# sensor.net
KiCad netlist of a schematic drawn in Altium Designer
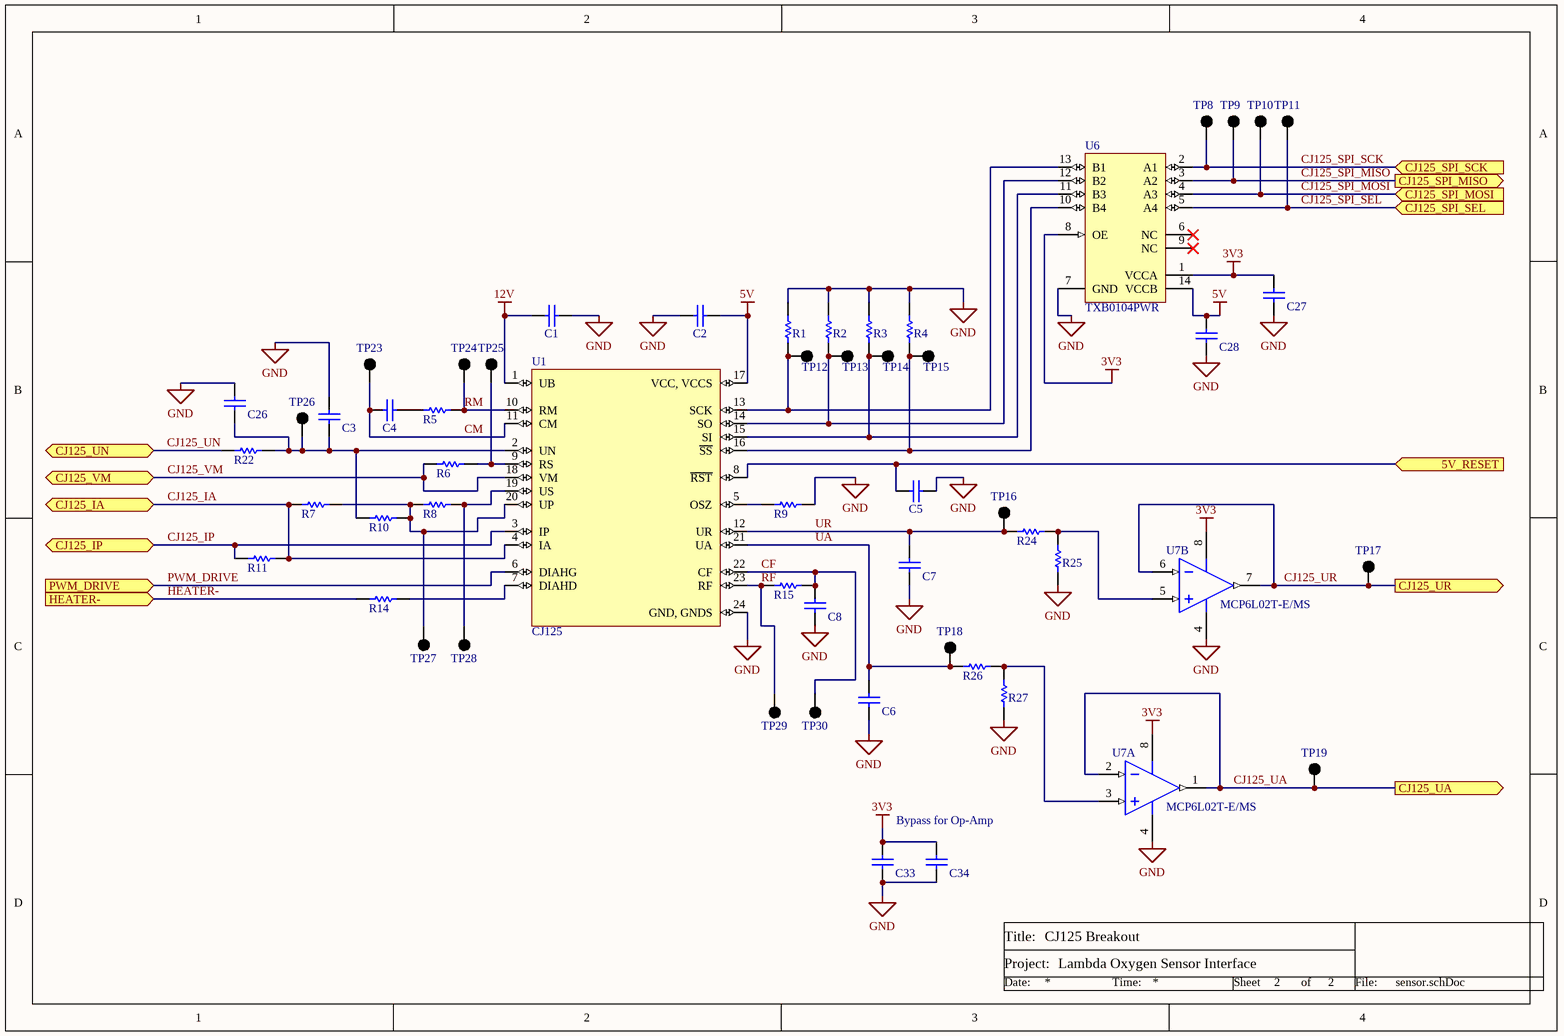
[diagram p0: sensor.schDoc]

(export (version "E")
  (design (tool "Eeschema 10.0.6"))
  (components
    (comp (ref "C1")
      (value "Generic 0805 Capacitor")
      (footprint "0805")
      (libsource (lib "symbol_library") (part "C_0805"))
    )
    (comp (ref "C2")
      (value "Generic 0805 Capacitor")
      (footprint "0805")
      (libsource (lib "symbol_library") (part "C_0805"))
    )
    (comp (ref "C3")
      (value "Generic 0805 Capacitor")
      (footprint "0805")
      (libsource (lib "symbol_library") (part "C_0805"))
    )
    (comp (ref "C4")
      (value "Generic 0805 Capacitor")
      (footprint "0805")
      (libsource (lib "symbol_library") (part "C_0805"))
    )
    (comp (ref "C5")
      (value "Generic 0805 Capacitor")
      (footprint "0805")
      (libsource (lib "symbol_library") (part "C_0805"))
    )
    (comp (ref "C6")
      (value "Generic 0805 Capacitor")
      (footprint "0805")
      (libsource (lib "symbol_library") (part "C_0805"))
    )
    (comp (ref "C7")
      (value "Generic 0805 Capacitor")
      (footprint "0805")
      (libsource (lib "symbol_library") (part "C_0805"))
    )
    (comp (ref "C8")
      (value "Generic 0805 Capacitor")
      (footprint "0805")
      (libsource (lib "symbol_library") (part "C_0805"))
    )
    (comp (ref "C26")
      (value "Generic 0805 Capacitor")
      (footprint "0805")
      (libsource (lib "symbol_library") (part "C_0805"))
    )
    (comp (ref "C27")
      (value "Generic 0805 Capacitor")
      (footprint "0805")
      (libsource (lib "symbol_library") (part "C_0805"))
    )
    (comp (ref "C28")
      (value "Generic 0805 Capacitor")
      (footprint "0805")
      (libsource (lib "symbol_library") (part "C_0805"))
    )
    (comp (ref "C33")
      (value "Generic 0805 Capacitor")
      (footprint "0805")
      (libsource (lib "symbol_library") (part "C_0805"))
    )
    (comp (ref "C34")
      (value "Generic 0805 Capacitor")
      (footprint "0805")
      (libsource (lib "symbol_library") (part "C_0805"))
    )
    (comp (ref "R1")
      (value "Generic 0603 Resistor")
      (footprint "0603")
      (libsource (lib "symbol_library") (part "R_0603"))
    )
    (comp (ref "R2")
      (value "Generic 0603 Resistor")
      (footprint "0603")
      (libsource (lib "symbol_library") (part "R_0603"))
    )
    (comp (ref "R3")
      (value "Generic 0603 Resistor")
      (footprint "0603")
      (libsource (lib "symbol_library") (part "R_0603"))
    )
    (comp (ref "R4")
      (value "Generic 0603 Resistor")
      (footprint "0603")
      (libsource (lib "symbol_library") (part "R_0603"))
    )
    (comp (ref "R5")
      (value "Generic 0603 Resistor")
      (footprint "0603")
      (libsource (lib "symbol_library") (part "R_0603"))
    )
    (comp (ref "R6")
      (value "Generic 0603 Resistor")
      (footprint "0603")
      (libsource (lib "symbol_library") (part "R_0603"))
    )
    (comp (ref "R7")
      (value "Generic 0603 Resistor")
      (footprint "0603")
      (libsource (lib "symbol_library") (part "R_0603"))
    )
    (comp (ref "R8")
      (value "Generic 0603 Resistor")
      (footprint "0603")
      (libsource (lib "symbol_library") (part "R_0603"))
    )
    (comp (ref "R9")
      (value "Generic 0603 Resistor")
      (footprint "0603")
      (libsource (lib "symbol_library") (part "R_0603"))
    )
    (comp (ref "R10")
      (value "Generic 0603 Resistor")
      (footprint "0603")
      (libsource (lib "symbol_library") (part "R_0603"))
    )
    (comp (ref "R11")
      (value "Generic 0603 Resistor")
      (footprint "0603")
      (libsource (lib "symbol_library") (part "R_0603"))
    )
    (comp (ref "R14")
      (value "Generic 0603 Resistor")
      (footprint "0603")
      (libsource (lib "symbol_library") (part "R_0603"))
    )
    (comp (ref "R15")
      (value "Generic 0603 Resistor")
      (footprint "0603")
      (libsource (lib "symbol_library") (part "R_0603"))
    )
    (comp (ref "R22")
      (value "Generic 0603 Resistor")
      (footprint "0603")
      (libsource (lib "symbol_library") (part "R_0603"))
    )
    (comp (ref "R24")
      (value "Generic 0603 Resistor")
      (footprint "0603")
      (libsource (lib "symbol_library") (part "R_0603"))
    )
    (comp (ref "R25")
      (value "Generic 0603 Resistor")
      (footprint "0603")
      (libsource (lib "symbol_library") (part "R_0603"))
    )
    (comp (ref "R26")
      (value "Generic 0603 Resistor")
      (footprint "0603")
      (libsource (lib "symbol_library") (part "R_0603"))
    )
    (comp (ref "R27")
      (value "Generic 0603 Resistor")
      (footprint "0603")
      (libsource (lib "symbol_library") (part "R_0603"))
    )
    (comp (ref "TP8")
      (value "5001")
      (footprint "KSTN-5001")
      (description "Test Point, Black, 1-Pin THD, RoHS, Bulk")
      (fields (field (name "MANUFACTURER") "Keystone"))
      (libsource (lib "symbol_library") (part "TP5001"))
    )
    (comp (ref "TP9")
      (value "5001")
      (footprint "KSTN-5001")
      (description "Test Point, Black, 1-Pin THD, RoHS, Bulk")
      (fields (field (name "MANUFACTURER") "Keystone"))
      (libsource (lib "symbol_library") (part "TP5001"))
    )
    (comp (ref "TP10")
      (value "5001")
      (footprint "KSTN-5001")
      (description "Test Point, Black, 1-Pin THD, RoHS, Bulk")
      (fields (field (name "MANUFACTURER") "Keystone"))
      (libsource (lib "symbol_library") (part "TP5001"))
    )
    (comp (ref "TP11")
      (value "5001")
      (footprint "KSTN-5001")
      (description "Test Point, Black, 1-Pin THD, RoHS, Bulk")
      (fields (field (name "MANUFACTURER") "Keystone"))
      (libsource (lib "symbol_library") (part "TP5001"))
    )
    (comp (ref "TP12")
      (value "5001")
      (footprint "KSTN-5001")
      (description "Test Point, Black, 1-Pin THD, RoHS, Bulk")
      (fields (field (name "MANUFACTURER") "Keystone"))
      (libsource (lib "symbol_library") (part "TP5001"))
    )
    (comp (ref "TP13")
      (value "5001")
      (footprint "KSTN-5001")
      (description "Test Point, Black, 1-Pin THD, RoHS, Bulk")
      (fields (field (name "MANUFACTURER") "Keystone"))
      (libsource (lib "symbol_library") (part "TP5001"))
    )
    (comp (ref "TP14")
      (value "5001")
      (footprint "KSTN-5001")
      (description "Test Point, Black, 1-Pin THD, RoHS, Bulk")
      (fields (field (name "MANUFACTURER") "Keystone"))
      (libsource (lib "symbol_library") (part "TP5001"))
    )
    (comp (ref "TP15")
      (value "5001")
      (footprint "KSTN-5001")
      (description "Test Point, Black, 1-Pin THD, RoHS, Bulk")
      (fields (field (name "MANUFACTURER") "Keystone"))
      (libsource (lib "symbol_library") (part "TP5001"))
    )
    (comp (ref "TP16")
      (value "5001")
      (footprint "KSTN-5001")
      (description "Test Point, Black, 1-Pin THD, RoHS, Bulk")
      (fields (field (name "MANUFACTURER") "Keystone"))
      (libsource (lib "symbol_library") (part "TP5001"))
    )
    (comp (ref "TP17")
      (value "5001")
      (footprint "KSTN-5001")
      (description "Test Point, Black, 1-Pin THD, RoHS, Bulk")
      (fields (field (name "MANUFACTURER") "Keystone"))
      (libsource (lib "symbol_library") (part "TP5001"))
    )
    (comp (ref "TP18")
      (value "5001")
      (footprint "KSTN-5001")
      (description "Test Point, Black, 1-Pin THD, RoHS, Bulk")
      (fields (field (name "MANUFACTURER") "Keystone"))
      (libsource (lib "symbol_library") (part "TP5001"))
    )
    (comp (ref "TP19")
      (value "5001")
      (footprint "KSTN-5001")
      (description "Test Point, Black, 1-Pin THD, RoHS, Bulk")
      (fields (field (name "MANUFACTURER") "Keystone"))
      (libsource (lib "symbol_library") (part "TP5001"))
    )
    (comp (ref "TP23")
      (value "5001")
      (footprint "KSTN-5001")
      (description "Test Point, Black, 1-Pin THD, RoHS, Bulk")
      (fields (field (name "MANUFACTURER") "Keystone"))
      (libsource (lib "symbol_library") (part "TP5001"))
    )
    (comp (ref "TP24")
      (value "5001")
      (footprint "KSTN-5001")
      (description "Test Point, Black, 1-Pin THD, RoHS, Bulk")
      (fields (field (name "MANUFACTURER") "Keystone"))
      (libsource (lib "symbol_library") (part "TP5001"))
    )
    (comp (ref "TP25")
      (value "5001")
      (footprint "KSTN-5001")
      (description "Test Point, Black, 1-Pin THD, RoHS, Bulk")
      (fields (field (name "MANUFACTURER") "Keystone"))
      (libsource (lib "symbol_library") (part "TP5001"))
    )
    (comp (ref "TP26")
      (value "5001")
      (footprint "KSTN-5001")
      (description "Test Point, Black, 1-Pin THD, RoHS, Bulk")
      (fields (field (name "MANUFACTURER") "Keystone"))
      (libsource (lib "symbol_library") (part "TP5001"))
    )
    (comp (ref "TP27")
      (value "5001")
      (footprint "KSTN-5001")
      (description "Test Point, Black, 1-Pin THD, RoHS, Bulk")
      (fields (field (name "MANUFACTURER") "Keystone"))
      (libsource (lib "symbol_library") (part "TP5001"))
    )
    (comp (ref "TP28")
      (value "5001")
      (footprint "KSTN-5001")
      (description "Test Point, Black, 1-Pin THD, RoHS, Bulk")
      (fields (field (name "MANUFACTURER") "Keystone"))
      (libsource (lib "symbol_library") (part "TP5001"))
    )
    (comp (ref "TP29")
      (value "5001")
      (footprint "KSTN-5001")
      (description "Test Point, Black, 1-Pin THD, RoHS, Bulk")
      (fields (field (name "MANUFACTURER") "Keystone"))
      (libsource (lib "symbol_library") (part "TP5001"))
    )
    (comp (ref "TP30")
      (value "5001")
      (footprint "KSTN-5001")
      (description "Test Point, Black, 1-Pin THD, RoHS, Bulk")
      (fields (field (name "MANUFACTURER") "Keystone"))
      (libsource (lib "symbol_library") (part "TP5001"))
    )
    (comp (ref "U1")
      (value "CJ125")
      (footprint "SOIC-24")
      (description "5V 2Mbaud SMT Lambda Probe Interface IC - SOIC-24")
      (libsource (lib "symbol_library") (part "CJ125"))
    )
    (comp (ref "U6")
      (value "TXB0104PWR")
      (footprint "PW0014A_M")
      (fields (field (name "MANUFACTURER") "Texas Instruments"))
      (libsource (lib "symbol_library") (part "TXB0104"))
    )
    (comp (ref "U7")
      (value "MCP6L02T-E/MS")
      (footprint "MSOP8_M")
      (description "1 MHz, 85 渭A Dual Op Amp, 8-Pin MSOP, Extended Temperature Range, Tape and Reel")
      (libsource (lib "symbol_library") (part "MCP6L02"))
    )
  )
  (nets
    (net (code "1") (name "/5V_RESET") (class "Default")
      (node (ref "C5") (pin "1") (pinfunction "1_1") (pintype "passive"))
      (node (ref "U1") (pin "8") (pinfunction "~{RST}_8") (pintype "bidirectional"))
    )
    (net (code "2") (name "/CF") (class "Default")
      (node (ref "C8") (pin "2") (pinfunction "2_2") (pintype "passive"))
      (node (ref "R15") (pin "2") (pinfunction "2_2") (pintype "passive"))
      (node (ref "TP30") (pin "1") (pintype "passive"))
      (node (ref "U1") (pin "22") (pinfunction "CF_22") (pintype "bidirectional"))
    )
    (net (code "3") (name "/CJ125_IA") (class "Default")
      (node (ref "R11") (pin "2") (pinfunction "2_2") (pintype "passive"))
      (node (ref "R7") (pin "1") (pinfunction "1_1") (pintype "passive"))
      (node (ref "U1") (pin "4") (pinfunction "IA_4") (pintype "bidirectional"))
    )
    (net (code "4") (name "/CJ125_IP") (class "Default")
      (node (ref "R11") (pin "1") (pinfunction "1_1") (pintype "passive"))
      (node (ref "U1") (pin "3") (pinfunction "IP_3") (pintype "bidirectional"))
    )
    (net (code "5") (name "/CJ125_SPI_MISO") (class "Default")
      (node (ref "TP9") (pin "1") (pintype "passive"))
      (node (ref "U6") (pin "3") (pinfunction "A2_3") (pintype "bidirectional"))
    )
    (net (code "6") (name "/CJ125_SPI_MOSI") (class "Default")
      (node (ref "TP10") (pin "1") (pintype "passive"))
      (node (ref "U6") (pin "4") (pinfunction "A3_4") (pintype "bidirectional"))
    )
    (net (code "7") (name "/CJ125_SPI_SCK") (class "Default")
      (node (ref "TP8") (pin "1") (pintype "passive"))
      (node (ref "U6") (pin "2") (pinfunction "A1_2") (pintype "bidirectional"))
    )
    (net (code "8") (name "/CJ125_SPI_SEL") (class "Default")
      (node (ref "TP11") (pin "1") (pintype "passive"))
      (node (ref "U6") (pin "5") (pinfunction "A4_5") (pintype "bidirectional"))
    )
    (net (code "9") (name "/CJ125_UA") (class "Default")
      (node (ref "TP19") (pin "1") (pintype "passive"))
      (node (ref "U7") (pin "1") (pinfunction "VOUTA_1") (pintype "output"))
      (node (ref "U7") (pin "2") (pinfunction "VINA-_2") (pintype "input"))
    )
    (net (code "10") (name "/CJ125_UN") (class "Default")
      (node (ref "R22") (pin "1") (pinfunction "1_1") (pintype "passive"))
    )
    (net (code "11") (name "/CJ125_UR") (class "Default")
      (node (ref "TP17") (pin "1") (pintype "passive"))
      (node (ref "U7") (pin "6") (pinfunction "VINB-_6") (pintype "input"))
      (node (ref "U7") (pin "7") (pinfunction "VOUTB_7") (pintype "output"))
    )
    (net (code "12") (name "/CJ125_VM") (class "Default")
      (node (ref "R6") (pin "1") (pinfunction "1_1") (pintype "passive"))
      (node (ref "U1") (pin "18") (pinfunction "VM_18") (pintype "bidirectional"))
    )
    (net (code "13") (name "/CM") (class "Default")
      (node (ref "C4") (pin "1") (pinfunction "1_1") (pintype "passive"))
      (node (ref "TP23") (pin "1") (pintype "passive"))
      (node (ref "U1") (pin "11") (pinfunction "CM_11") (pintype "bidirectional"))
    )
    (net (code "14") (name "/HEATER-") (class "Default")
      (node (ref "R14") (pin "1") (pinfunction "1_1") (pintype "passive"))
    )
    (net (code "15") (name "/PWM_DRIVE") (class "Default")
      (node (ref "U1") (pin "6") (pinfunction "DIAHG_6") (pintype "bidirectional"))
    )
    (net (code "16") (name "/RF") (class "Default")
      (node (ref "R15") (pin "1") (pinfunction "1_1") (pintype "passive"))
      (node (ref "TP29") (pin "1") (pintype "passive"))
      (node (ref "U1") (pin "23") (pinfunction "RF_23") (pintype "bidirectional"))
    )
    (net (code "17") (name "/RM") (class "Default")
      (node (ref "R5") (pin "2") (pinfunction "2_2") (pintype "passive"))
      (node (ref "TP24") (pin "1") (pintype "passive"))
      (node (ref "U1") (pin "10") (pinfunction "RM_10") (pintype "bidirectional"))
    )
    (net (code "18") (name "/UA") (class "Default")
      (node (ref "C6") (pin "2") (pinfunction "2_2") (pintype "passive"))
      (node (ref "R26") (pin "1") (pinfunction "1_1") (pintype "passive"))
      (node (ref "TP18") (pin "1") (pintype "passive"))
      (node (ref "U1") (pin "21") (pinfunction "UA_21") (pintype "bidirectional"))
    )
    (net (code "19") (name "/UR") (class "Default")
      (node (ref "C7") (pin "2") (pinfunction "2_2") (pintype "passive"))
      (node (ref "R24") (pin "1") (pinfunction "1_1") (pintype "passive"))
      (node (ref "TP16") (pin "1") (pintype "passive"))
      (node (ref "U1") (pin "12") (pinfunction "UR_12") (pintype "bidirectional"))
    )
    (net (code "20") (name "3V3") (class "Default")
      (node (ref "C27") (pin "2") (pinfunction "2_2") (pintype "passive"))
      (node (ref "C33") (pin "2") (pinfunction "2_2") (pintype "passive"))
      (node (ref "C34") (pin "2") (pinfunction "2_2") (pintype "passive"))
      (node (ref "U6") (pin "1") (pinfunction "VCCA_1") (pintype "power_in"))
      (node (ref "U6") (pin "8") (pinfunction "OE_8") (pintype "input"))
      (node (ref "U7") (pin "8") (pinfunction "VDD_8") (pintype "power_in"))
    )
    (net (code "21") (name "5V") (class "Default")
      (node (ref "C2") (pin "1") (pinfunction "1_1") (pintype "passive"))
      (node (ref "C28") (pin "2") (pinfunction "2_2") (pintype "passive"))
      (node (ref "U1") (pin "17") (pinfunction "VCC,_VCCS_17") (pintype "bidirectional"))
      (node (ref "U6") (pin "14") (pinfunction "VCCB_14") (pintype "power_in"))
    )
    (net (code "22") (name "12V") (class "Default")
      (node (ref "C1") (pin "2") (pinfunction "2_2") (pintype "passive"))
      (node (ref "U1") (pin "1") (pinfunction "UB_1") (pintype "bidirectional"))
    )
    (net (code "23") (name "GND") (class "Default")
      (node (ref "C1") (pin "1") (pinfunction "1_1") (pintype "passive"))
      (node (ref "C2") (pin "2") (pinfunction "2_2") (pintype "passive"))
      (node (ref "C26") (pin "2") (pinfunction "2_2") (pintype "passive"))
      (node (ref "C27") (pin "1") (pinfunction "1_1") (pintype "passive"))
      (node (ref "C28") (pin "1") (pinfunction "1_1") (pintype "passive"))
      (node (ref "C3") (pin "2") (pinfunction "2_2") (pintype "passive"))
      (node (ref "C33") (pin "1") (pinfunction "1_1") (pintype "passive"))
      (node (ref "C34") (pin "1") (pinfunction "1_1") (pintype "passive"))
      (node (ref "C5") (pin "2") (pinfunction "2_2") (pintype "passive"))
      (node (ref "C6") (pin "1") (pinfunction "1_1") (pintype "passive"))
      (node (ref "C7") (pin "1") (pinfunction "1_1") (pintype "passive"))
      (node (ref "C8") (pin "1") (pinfunction "1_1") (pintype "passive"))
      (node (ref "R1") (pin "2") (pinfunction "2_2") (pintype "passive"))
      (node (ref "R2") (pin "2") (pinfunction "2_2") (pintype "passive"))
      (node (ref "R25") (pin "1") (pinfunction "1_1") (pintype "passive"))
      (node (ref "R27") (pin "1") (pinfunction "1_1") (pintype "passive"))
      (node (ref "R3") (pin "2") (pinfunction "2_2") (pintype "passive"))
      (node (ref "R4") (pin "2") (pinfunction "2_2") (pintype "passive"))
      (node (ref "R9") (pin "2") (pinfunction "2_2") (pintype "passive"))
      (node (ref "U1") (pin "24") (pinfunction "GND,_GNDS_24") (pintype "bidirectional"))
      (node (ref "U6") (pin "7") (pinfunction "GND_7") (pintype "power_in"))
      (node (ref "U7") (pin "4") (pinfunction "VSS_4") (pintype "power_in"))
    )
    (net (code "24") (name "Net-(C4-Pad2)") (class "Default")
      (node (ref "C4") (pin "2") (pinfunction "2_2") (pintype "passive"))
      (node (ref "R5") (pin "1") (pinfunction "1_1") (pintype "passive"))
    )
    (net (code "25") (name "Net-(U1-DIAHD)") (class "Default")
      (node (ref "R14") (pin "2") (pinfunction "2_2") (pintype "passive"))
      (node (ref "U1") (pin "7") (pinfunction "DIAHD_7") (pintype "bidirectional"))
    )
    (net (code "26") (name "Net-(U1-OSZ)") (class "Default")
      (node (ref "R9") (pin "1") (pinfunction "1_1") (pintype "passive"))
      (node (ref "U1") (pin "5") (pinfunction "OSZ_5") (pintype "bidirectional"))
    )
    (net (code "27") (name "Net-(U1-RS)") (class "Default")
      (node (ref "R6") (pin "2") (pinfunction "2_2") (pintype "passive"))
      (node (ref "TP25") (pin "1") (pintype "passive"))
      (node (ref "U1") (pin "9") (pinfunction "RS_9") (pintype "bidirectional"))
    )
    (net (code "28") (name "Net-(U1-SCK)") (class "Default")
      (node (ref "R1") (pin "1") (pinfunction "1_1") (pintype "passive"))
      (node (ref "TP12") (pin "1") (pintype "passive"))
      (node (ref "U1") (pin "13") (pinfunction "SCK_13") (pintype "bidirectional"))
      (node (ref "U6") (pin "13") (pinfunction "B1_13") (pintype "bidirectional"))
    )
    (net (code "29") (name "Net-(U1-SI)") (class "Default")
      (node (ref "R3") (pin "1") (pinfunction "1_1") (pintype "passive"))
      (node (ref "TP14") (pin "1") (pintype "passive"))
      (node (ref "U1") (pin "15") (pinfunction "SI_15") (pintype "bidirectional"))
      (node (ref "U6") (pin "11") (pinfunction "B3_11") (pintype "bidirectional"))
    )
    (net (code "30") (name "Net-(U1-SO)") (class "Default")
      (node (ref "R2") (pin "1") (pinfunction "1_1") (pintype "passive"))
      (node (ref "TP13") (pin "1") (pintype "passive"))
      (node (ref "U1") (pin "14") (pinfunction "SO_14") (pintype "bidirectional"))
      (node (ref "U6") (pin "12") (pinfunction "B2_12") (pintype "bidirectional"))
    )
    (net (code "31") (name "Net-(U1-UN)") (class "Default")
      (node (ref "C26") (pin "1") (pinfunction "1_1") (pintype "passive"))
      (node (ref "C3") (pin "1") (pinfunction "1_1") (pintype "passive"))
      (node (ref "R10") (pin "1") (pinfunction "1_1") (pintype "passive"))
      (node (ref "R22") (pin "2") (pinfunction "2_2") (pintype "passive"))
      (node (ref "TP26") (pin "1") (pintype "passive"))
      (node (ref "U1") (pin "2") (pinfunction "UN_2") (pintype "bidirectional"))
    )
    (net (code "32") (name "Net-(U1-UP)") (class "Default")
      (node (ref "R10") (pin "2") (pinfunction "2_2") (pintype "passive"))
      (node (ref "R7") (pin "2") (pinfunction "2_2") (pintype "passive"))
      (node (ref "R8") (pin "1") (pinfunction "1_1") (pintype "passive"))
      (node (ref "TP27") (pin "1") (pintype "passive"))
      (node (ref "U1") (pin "20") (pinfunction "UP_20") (pintype "bidirectional"))
    )
    (net (code "33") (name "Net-(U1-US)") (class "Default")
      (node (ref "R8") (pin "2") (pinfunction "2_2") (pintype "passive"))
      (node (ref "TP28") (pin "1") (pintype "passive"))
      (node (ref "U1") (pin "19") (pinfunction "US_19") (pintype "bidirectional"))
    )
    (net (code "34") (name "Net-(U1-~{SS})") (class "Default")
      (node (ref "R4") (pin "1") (pinfunction "1_1") (pintype "passive"))
      (node (ref "TP15") (pin "1") (pintype "passive"))
      (node (ref "U1") (pin "16") (pinfunction "~{SS}_16") (pintype "bidirectional"))
      (node (ref "U6") (pin "10") (pinfunction "B4_10") (pintype "bidirectional"))
    )
    (net (code "35") (name "Net-(U7A-VINA+)") (class "Default")
      (node (ref "R26") (pin "2") (pinfunction "2_2") (pintype "passive"))
      (node (ref "R27") (pin "2") (pinfunction "2_2") (pintype "passive"))
      (node (ref "U7") (pin "3") (pinfunction "VINA+_3") (pintype "input"))
    )
    (net (code "36") (name "Net-(U7B-VINB+)") (class "Default")
      (node (ref "R24") (pin "2") (pinfunction "2_2") (pintype "passive"))
      (node (ref "R25") (pin "2") (pinfunction "2_2") (pintype "passive"))
      (node (ref "U7") (pin "5") (pinfunction "VINB+_5") (pintype "input"))
    )
    (net (code "37") (name "unconnected-(U6-NC-Pad6)") (class "Default")
      (node (ref "U6") (pin "6") (pinfunction "NC_6") (pintype "passive+no_connect"))
    )
    (net (code "38") (name "unconnected-(U6-NC-Pad9)") (class "Default")
      (node (ref "U6") (pin "9") (pinfunction "NC_9") (pintype "passive+no_connect"))
    )
  )
)
